# deneme4.net
KiCad netlist of a schematic drawn in EAGLE
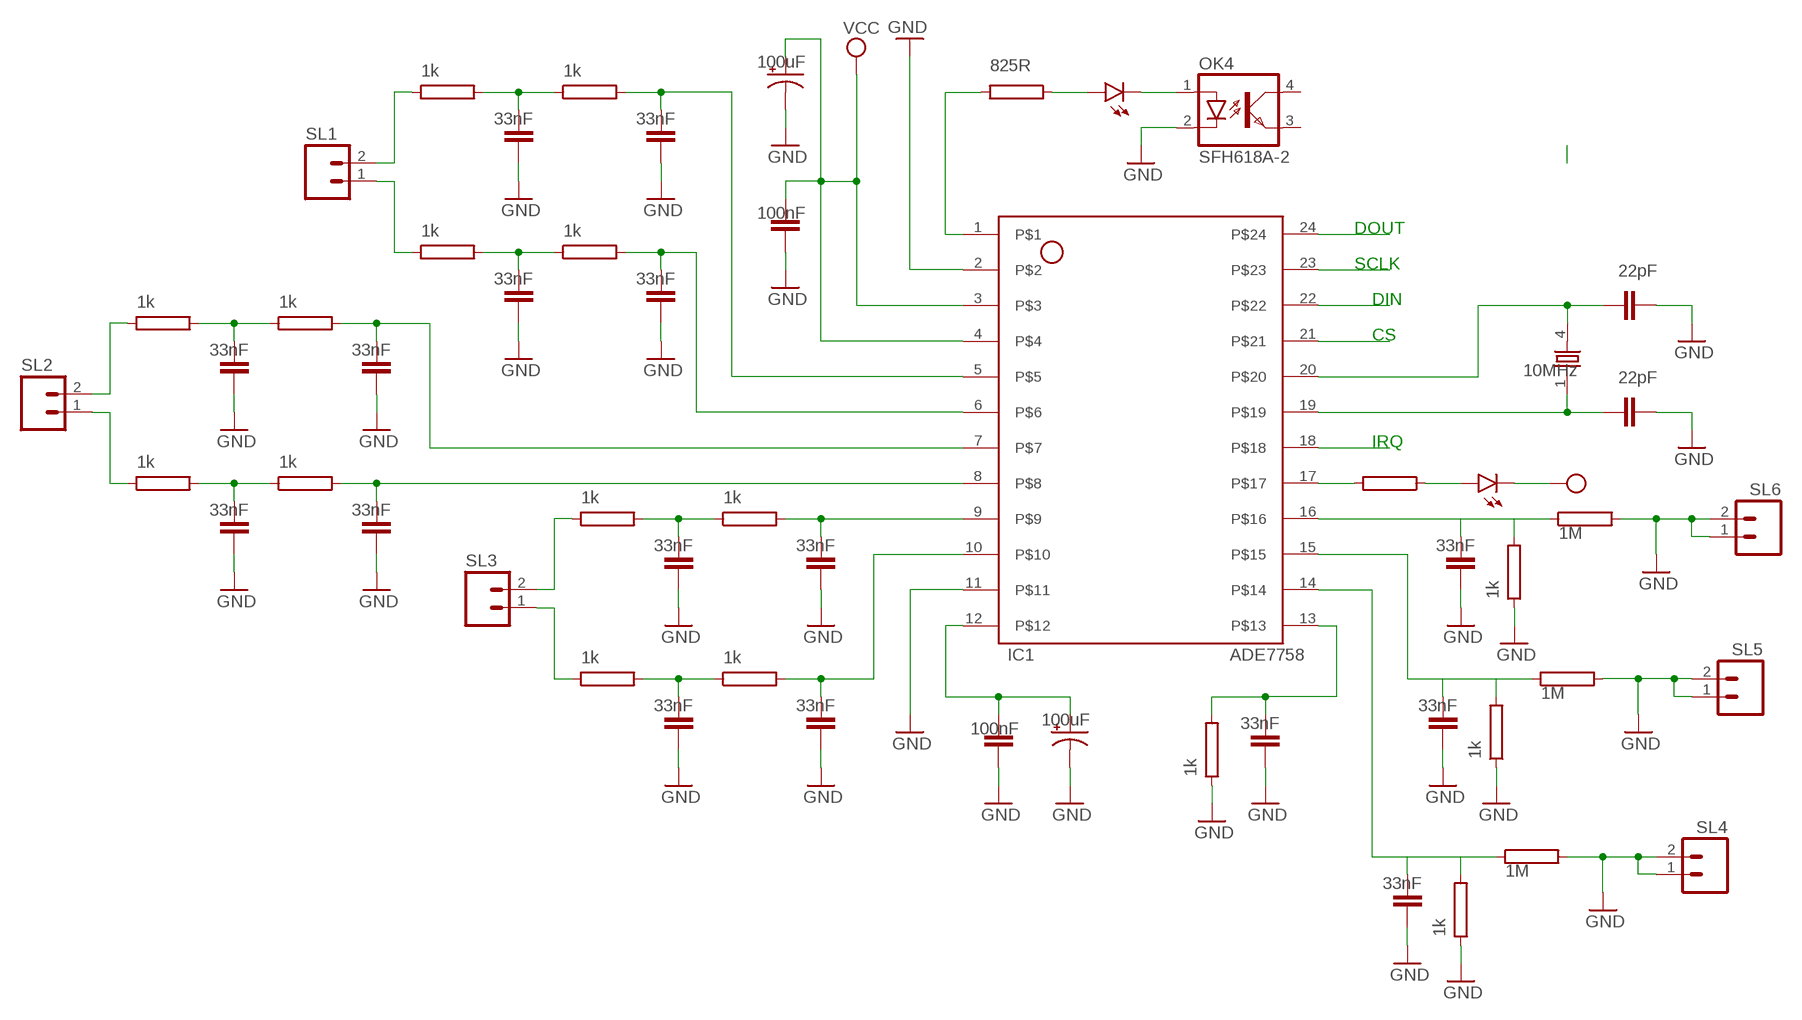
[diagram p0: schematic, sheet 1]

(export (version "E")
  (design (tool "Eeschema 10.0.6"))
  (components
    (comp (ref "C1")
      (value "100nF")
      (footprint "eagle-import:C2.5-3")
      (libsource (lib "eagle-import") (part "C2,5-3"))
    )
    (comp (ref "C2")
      (value "33nF")
      (footprint "eagle-import:C2.5-3")
      (libsource (lib "eagle-import") (part "C2,5-3"))
    )
    (comp (ref "C4")
      (value "33nF")
      (footprint "eagle-import:C2.5-3")
      (libsource (lib "eagle-import") (part "C2,5-3"))
    )
    (comp (ref "C5")
      (value "33nF")
      (footprint "eagle-import:C2.5-3")
      (libsource (lib "eagle-import") (part "C2,5-3"))
    )
    (comp (ref "C6")
      (value "33nF")
      (footprint "eagle-import:C2.5-3")
      (libsource (lib "eagle-import") (part "C2,5-3"))
    )
    (comp (ref "C7")
      (value "33nF")
      (footprint "eagle-import:C2.5-3")
      (libsource (lib "eagle-import") (part "C2,5-3"))
    )
    (comp (ref "C8")
      (value "22pF")
      (footprint "eagle-import:C2.5-3")
      (libsource (lib "eagle-import") (part "C2,5-3"))
    )
    (comp (ref "C9")
      (value "22pF")
      (footprint "eagle-import:C2.5-3")
      (libsource (lib "eagle-import") (part "C2,5-3"))
    )
    (comp (ref "C14")
      (value "100uF")
      (footprint "eagle-import:085CS_1AR")
      (libsource (lib "eagle-import") (part "CPOL-US085CS-1AR"))
    )
    (comp (ref "C16")
      (value "33nF")
      (footprint "eagle-import:C2.5-3")
      (libsource (lib "eagle-import") (part "C2,5-3"))
    )
    (comp (ref "C17")
      (value "33nF")
      (footprint "eagle-import:C2.5-3")
      (libsource (lib "eagle-import") (part "C2,5-3"))
    )
    (comp (ref "C18")
      (value "33nF")
      (footprint "eagle-import:C2.5-3")
      (libsource (lib "eagle-import") (part "C2,5-3"))
    )
    (comp (ref "C19")
      (value "33nF")
      (footprint "eagle-import:C2.5-3")
      (libsource (lib "eagle-import") (part "C2,5-3"))
    )
    (comp (ref "C20")
      (value "33nF")
      (footprint "eagle-import:C2.5-3")
      (libsource (lib "eagle-import") (part "C2,5-3"))
    )
    (comp (ref "C21")
      (value "33nF")
      (footprint "eagle-import:C2.5-3")
      (libsource (lib "eagle-import") (part "C2,5-3"))
    )
    (comp (ref "C22")
      (value "33nF")
      (footprint "eagle-import:C2.5-3")
      (libsource (lib "eagle-import") (part "C2,5-3"))
    )
    (comp (ref "C23")
      (value "100uF")
      (footprint "eagle-import:085CS_1AR")
      (libsource (lib "eagle-import") (part "CPOL-US085CS-1AR"))
    )
    (comp (ref "C24")
      (value "100nF")
      (footprint "eagle-import:C2.5-3")
      (libsource (lib "eagle-import") (part "C2,5-3"))
    )
    (comp (ref "C25")
      (value "33nF")
      (footprint "eagle-import:C2.5-3")
      (libsource (lib "eagle-import") (part "C2,5-3"))
    )
    (comp (ref "C26")
      (value "33nF")
      (footprint "eagle-import:C2.5-3")
      (libsource (lib "eagle-import") (part "C2,5-3"))
    )
    (comp (ref "C27")
      (value "33nF")
      (footprint "eagle-import:C2.5-3")
      (libsource (lib "eagle-import") (part "C2,5-3"))
    )
    (comp (ref "C28")
      (value "33nF")
      (footprint "eagle-import:C2.5-3")
      (libsource (lib "eagle-import") (part "C2,5-3"))
    )
    (comp (ref "IC1")
      (value "ADE7758")
      (footprint "eagle-import:ADE7758ARWZ")
      (fields (field (name "MF") "ADI Electronics"))
      (libsource (lib "eagle-import") (part "ADE7758"))
    )
    (comp (ref "LED1")
      (value "LAP4-BOTTOM")
      (footprint "eagle-import:P47F-BOTTOM")
      (libsource (lib "eagle-import") (part "P4-BOTTOMLA"))
    )
    (comp (ref "LED2")
      (value "LAP4-BOTTOM")
      (footprint "eagle-import:P47F-BOTTOM")
      (libsource (lib "eagle-import") (part "P4-BOTTOMLA"))
    )
    (comp (ref "OK4")
      (value "SFH618A-2")
      (footprint "eagle-import:DIP4")
      (fields (field (name "MF") "VISHAY/TELEFUNKEN"))
      (libsource (lib "eagle-import") (part "SFH618?A-2"))
    )
    (comp (ref "Q1")
      (value "10MHz")
      (footprint "eagle-import:86SMX")
      (fields (field (name "MF") "C-MAC  FREQUENCY PRODUCTS LTD") (field (name "MPN") "XTAL003321- 86SMX"))
      (libsource (lib "eagle-import") (part "86SMX"))
    )
    (comp (ref "R1")
      (value "825R")
      (footprint "eagle-import:TO-247-2V")
      (libsource (lib "eagle-import") (part "RMG100-V"))
    )
    (comp (ref "R2")
      (value "1k")
      (footprint "eagle-import:TO-247-2V")
      (libsource (lib "eagle-import") (part "RMG100-V"))
    )
    (comp (ref "R3")
      (value "1k")
      (footprint "eagle-import:TO-247-2V")
      (libsource (lib "eagle-import") (part "RMG100-V"))
    )
    (comp (ref "R4")
      (value "1k")
      (footprint "eagle-import:TO-247-2V")
      (libsource (lib "eagle-import") (part "RMG100-V"))
    )
    (comp (ref "R5")
      (value "1k")
      (footprint "eagle-import:TO-247-2V")
      (libsource (lib "eagle-import") (part "RMG100-V"))
    )
    (comp (ref "R6")
      (value "1k")
      (footprint "eagle-import:TO-247-2V")
      (libsource (lib "eagle-import") (part "RMG100-V"))
    )
    (comp (ref "R7")
      (value "1k")
      (footprint "eagle-import:TO-247-2V")
      (libsource (lib "eagle-import") (part "RMG100-V"))
    )
    (comp (ref "R8")
      (value "1k")
      (footprint "eagle-import:TO-247-2V")
      (libsource (lib "eagle-import") (part "RMG100-V"))
    )
    (comp (ref "R9")
      (value "1k")
      (footprint "eagle-import:TO-247-2V")
      (libsource (lib "eagle-import") (part "RMG100-V"))
    )
    (comp (ref "R10")
      (value "1k")
      (footprint "eagle-import:TO-247-2V")
      (libsource (lib "eagle-import") (part "RMG100-V"))
    )
    (comp (ref "R11")
      (value "1k")
      (footprint "eagle-import:TO-247-2V")
      (libsource (lib "eagle-import") (part "RMG100-V"))
    )
    (comp (ref "R12")
      (value "1k")
      (footprint "eagle-import:TO-247-2V")
      (libsource (lib "eagle-import") (part "RMG100-V"))
    )
    (comp (ref "R13")
      (value "1k")
      (footprint "eagle-import:TO-247-2V")
      (libsource (lib "eagle-import") (part "RMG100-V"))
    )
    (comp (ref "R14")
      (value "1k")
      (footprint "eagle-import:TO-247-2V")
      (libsource (lib "eagle-import") (part "RMG100-V"))
    )
    (comp (ref "R15")
      (value "1k")
      (footprint "eagle-import:TO-247-2V")
      (libsource (lib "eagle-import") (part "RMG100-V"))
    )
    (comp (ref "R16")
      (value "1M")
      (footprint "eagle-import:TO-247-2V")
      (libsource (lib "eagle-import") (part "RMG100-V"))
    )
    (comp (ref "R17")
      (value "1k")
      (footprint "eagle-import:TO-247-2V")
      (libsource (lib "eagle-import") (part "RMG100-V"))
    )
    (comp (ref "R18")
      (value "1M")
      (footprint "eagle-import:TO-247-2V")
      (libsource (lib "eagle-import") (part "RMG100-V"))
    )
    (comp (ref "R19")
      (value "1k")
      (footprint "eagle-import:TO-247-2V")
      (libsource (lib "eagle-import") (part "RMG100-V"))
    )
    (comp (ref "R20")
      (value "1M")
      (footprint "eagle-import:TO-247-2V")
      (libsource (lib "eagle-import") (part "RMG100-V"))
    )
    (comp (ref "R21")
      (value "825R")
      (footprint "eagle-import:TO-247-2V")
      (libsource (lib "eagle-import") (part "RMG100-V"))
    )
    (comp (ref "SL1")
      (value "M02")
      (footprint "eagle-import:02P")
      (libsource (lib "eagle-import") (part "M02"))
    )
    (comp (ref "SL2")
      (value "M02")
      (footprint "eagle-import:02P")
      (libsource (lib "eagle-import") (part "M02"))
    )
    (comp (ref "SL3")
      (value "M02")
      (footprint "eagle-import:02P")
      (libsource (lib "eagle-import") (part "M02"))
    )
    (comp (ref "SL4")
      (value "M02")
      (footprint "eagle-import:02P")
      (libsource (lib "eagle-import") (part "M02"))
    )
    (comp (ref "SL5")
      (value "M02")
      (footprint "eagle-import:02P")
      (libsource (lib "eagle-import") (part "M02"))
    )
    (comp (ref "SL6")
      (value "M02")
      (footprint "eagle-import:02P")
      (libsource (lib "eagle-import") (part "M02"))
    )
  )
  (nets
    (net (code "1") (name "GND") (class "Default")
      (node (ref "C1") (pin "1") (pinfunction "1_1") (pintype "passive"))
      (node (ref "C14") (pin "-") (pinfunction "-_-") (pintype "passive"))
      (node (ref "C16") (pin "2") (pinfunction "2_2") (pintype "passive"))
      (node (ref "C17") (pin "2") (pinfunction "2_2") (pintype "passive"))
      (node (ref "C18") (pin "2") (pinfunction "2_2") (pintype "passive"))
      (node (ref "C19") (pin "2") (pinfunction "2_2") (pintype "passive"))
      (node (ref "C2") (pin "2") (pinfunction "2_2") (pintype "passive"))
      (node (ref "C20") (pin "2") (pinfunction "2_2") (pintype "passive"))
      (node (ref "C21") (pin "2") (pinfunction "2_2") (pintype "passive"))
      (node (ref "C22") (pin "2") (pinfunction "2_2") (pintype "passive"))
      (node (ref "C23") (pin "-") (pinfunction "-_-") (pintype "passive"))
      (node (ref "C24") (pin "1") (pinfunction "1_1") (pintype "passive"))
      (node (ref "C25") (pin "2") (pinfunction "2_2") (pintype "passive"))
      (node (ref "C26") (pin "2") (pinfunction "2_2") (pintype "passive"))
      (node (ref "C27") (pin "2") (pinfunction "2_2") (pintype "passive"))
      (node (ref "C28") (pin "2") (pinfunction "2_2") (pintype "passive"))
      (node (ref "C4") (pin "2") (pinfunction "2_2") (pintype "passive"))
      (node (ref "C5") (pin "2") (pinfunction "2_2") (pintype "passive"))
      (node (ref "C6") (pin "2") (pinfunction "2_2") (pintype "passive"))
      (node (ref "C7") (pin "2") (pinfunction "2_2") (pintype "passive"))
      (node (ref "C8") (pin "2") (pinfunction "2_2") (pintype "passive"))
      (node (ref "C9") (pin "2") (pinfunction "2_2") (pintype "passive"))
      (node (ref "IC1") (pin "11") (pinfunction "P$11_11") (pintype "bidirectional"))
      (node (ref "IC1") (pin "2") (pinfunction "P$2_2") (pintype "bidirectional"))
      (node (ref "OK4") (pin "2") (pinfunction "C_2") (pintype "passive"))
      (node (ref "R14") (pin "1") (pinfunction "1_1") (pintype "passive"))
      (node (ref "R15") (pin "1") (pinfunction "1_1") (pintype "passive"))
      (node (ref "R16") (pin "2") (pinfunction "2_2") (pintype "passive"))
      (node (ref "R17") (pin "1") (pinfunction "1_1") (pintype "passive"))
      (node (ref "R18") (pin "2") (pinfunction "2_2") (pintype "passive"))
      (node (ref "R19") (pin "1") (pinfunction "1_1") (pintype "passive"))
      (node (ref "R20") (pin "2") (pinfunction "2_2") (pintype "passive"))
      (node (ref "SL4") (pin "1") (pinfunction "1_1") (pintype "passive"))
      (node (ref "SL4") (pin "2") (pinfunction "2_2") (pintype "passive"))
      (node (ref "SL5") (pin "1") (pinfunction "1_1") (pintype "passive"))
      (node (ref "SL5") (pin "2") (pinfunction "2_2") (pintype "passive"))
      (node (ref "SL6") (pin "1") (pinfunction "1_1") (pintype "passive"))
      (node (ref "SL6") (pin "2") (pinfunction "2_2") (pintype "passive"))
    )
    (net (code "2") (name "Net-(C16-Pad1)") (class "Default")
      (node (ref "C16") (pin "1") (pinfunction "1_1") (pintype "passive"))
      (node (ref "R2") (pin "1") (pinfunction "1_1") (pintype "passive"))
      (node (ref "R3") (pin "2") (pinfunction "2_2") (pintype "passive"))
    )
    (net (code "3") (name "Net-(C18-Pad1)") (class "Default")
      (node (ref "C18") (pin "1") (pinfunction "1_1") (pintype "passive"))
      (node (ref "R4") (pin "1") (pinfunction "1_1") (pintype "passive"))
      (node (ref "R5") (pin "2") (pinfunction "2_2") (pintype "passive"))
    )
    (net (code "4") (name "Net-(C20-Pad1)") (class "Default")
      (node (ref "C20") (pin "1") (pinfunction "1_1") (pintype "passive"))
      (node (ref "R6") (pin "1") (pinfunction "1_1") (pintype "passive"))
      (node (ref "R7") (pin "2") (pinfunction "2_2") (pintype "passive"))
    )
    (net (code "5") (name "Net-(C22-Pad1)") (class "Default")
      (node (ref "C22") (pin "1") (pinfunction "1_1") (pintype "passive"))
      (node (ref "R8") (pin "1") (pinfunction "1_1") (pintype "passive"))
      (node (ref "R9") (pin "2") (pinfunction "2_2") (pintype "passive"))
    )
    (net (code "6") (name "Net-(C26-Pad1)") (class "Default")
      (node (ref "C26") (pin "1") (pinfunction "1_1") (pintype "passive"))
      (node (ref "R10") (pin "1") (pinfunction "1_1") (pintype "passive"))
      (node (ref "R11") (pin "2") (pinfunction "2_2") (pintype "passive"))
    )
    (net (code "7") (name "Net-(C28-Pad1)") (class "Default")
      (node (ref "C28") (pin "1") (pinfunction "1_1") (pintype "passive"))
      (node (ref "R12") (pin "1") (pinfunction "1_1") (pintype "passive"))
      (node (ref "R13") (pin "2") (pinfunction "2_2") (pintype "passive"))
    )
    (net (code "8") (name "Net-(IC1-P$1)") (class "Default")
      (node (ref "IC1") (pin "1") (pinfunction "P$1_1") (pintype "bidirectional"))
      (node (ref "R1") (pin "2") (pinfunction "2_2") (pintype "passive"))
    )
    (net (code "9") (name "Net-(IC1-P$5)") (class "Default")
      (node (ref "C2") (pin "1") (pinfunction "1_1") (pintype "passive"))
      (node (ref "IC1") (pin "5") (pinfunction "P$5_5") (pintype "bidirectional"))
      (node (ref "R2") (pin "2") (pinfunction "2_2") (pintype "passive"))
    )
    (net (code "10") (name "Net-(IC1-P$6)") (class "Default")
      (node (ref "C17") (pin "1") (pinfunction "1_1") (pintype "passive"))
      (node (ref "IC1") (pin "6") (pinfunction "P$6_6") (pintype "bidirectional"))
      (node (ref "R4") (pin "2") (pinfunction "2_2") (pintype "passive"))
    )
    (net (code "11") (name "Net-(IC1-P$7)") (class "Default")
      (node (ref "C19") (pin "1") (pinfunction "1_1") (pintype "passive"))
      (node (ref "IC1") (pin "7") (pinfunction "P$7_7") (pintype "bidirectional"))
      (node (ref "R6") (pin "2") (pinfunction "2_2") (pintype "passive"))
    )
    (net (code "12") (name "Net-(IC1-P$8)") (class "Default")
      (node (ref "C21") (pin "1") (pinfunction "1_1") (pintype "passive"))
      (node (ref "IC1") (pin "8") (pinfunction "P$8_8") (pintype "bidirectional"))
      (node (ref "R8") (pin "2") (pinfunction "2_2") (pintype "passive"))
    )
    (net (code "13") (name "Net-(IC1-P$9)") (class "Default")
      (node (ref "C25") (pin "1") (pinfunction "1_1") (pintype "passive"))
      (node (ref "IC1") (pin "9") (pinfunction "P$9_9") (pintype "bidirectional"))
      (node (ref "R10") (pin "2") (pinfunction "2_2") (pintype "passive"))
    )
    (net (code "14") (name "Net-(IC1-P$10)") (class "Default")
      (node (ref "C27") (pin "1") (pinfunction "1_1") (pintype "passive"))
      (node (ref "IC1") (pin "10") (pinfunction "P$10_10") (pintype "bidirectional"))
      (node (ref "R12") (pin "2") (pinfunction "2_2") (pintype "passive"))
    )
    (net (code "15") (name "Net-(IC1-P$12)") (class "Default")
      (node (ref "C23") (pin "+") (pinfunction "+_+") (pintype "passive"))
      (node (ref "C24") (pin "2") (pinfunction "2_2") (pintype "passive"))
      (node (ref "IC1") (pin "12") (pinfunction "P$12_12") (pintype "bidirectional"))
    )
    (net (code "16") (name "Net-(IC1-P$13)") (class "Default")
      (node (ref "C4") (pin "1") (pinfunction "1_1") (pintype "passive"))
      (node (ref "IC1") (pin "13") (pinfunction "P$13_13") (pintype "bidirectional"))
      (node (ref "R14") (pin "2") (pinfunction "2_2") (pintype "passive"))
    )
    (net (code "17") (name "Net-(IC1-P$14)") (class "Default")
      (node (ref "IC1") (pin "14") (pinfunction "P$14_14") (pintype "bidirectional"))
      (node (ref "R18") (pin "1") (pinfunction "1_1") (pintype "passive"))
    )
    (net (code "18") (name "Net-(IC1-P$15)") (class "Default")
      (node (ref "IC1") (pin "15") (pinfunction "P$15_15") (pintype "bidirectional"))
      (node (ref "R16") (pin "1") (pinfunction "1_1") (pintype "passive"))
    )
    (net (code "19") (name "Net-(IC1-P$16)") (class "Default")
      (node (ref "IC1") (pin "16") (pinfunction "P$16_16") (pintype "bidirectional"))
      (node (ref "R20") (pin "1") (pinfunction "1_1") (pintype "passive"))
    )
    (net (code "20") (name "Net-(IC1-P$17)") (class "Default")
      (node (ref "IC1") (pin "17") (pinfunction "P$17_17") (pintype "bidirectional"))
      (node (ref "R21") (pin "2") (pinfunction "2_2") (pintype "passive"))
    )
    (net (code "21") (name "Net-(IC1-P$19)") (class "Default")
      (node (ref "C8") (pin "1") (pinfunction "1_1") (pintype "passive"))
      (node (ref "IC1") (pin "19") (pinfunction "P$19_19") (pintype "bidirectional"))
      (node (ref "Q1") (pin "1") (pinfunction "1_1") (pintype "passive"))
    )
    (net (code "22") (name "Net-(IC1-P$20)") (class "Default")
      (node (ref "C9") (pin "1") (pinfunction "1_1") (pintype "passive"))
      (node (ref "IC1") (pin "20") (pinfunction "P$20_20") (pintype "bidirectional"))
      (node (ref "Q1") (pin "4") (pinfunction "2_4") (pintype "passive"))
    )
    (net (code "23") (name "Net-(LED1-PadA)") (class "Default")
      (node (ref "LED1") (pin "A") (pinfunction "A_A") (pintype "passive"))
      (node (ref "R1") (pin "1") (pinfunction "1_1") (pintype "passive"))
    )
    (net (code "24") (name "Net-(LED2-PadA)") (class "Default")
      (node (ref "LED2") (pin "A") (pinfunction "A_A") (pintype "passive"))
      (node (ref "R21") (pin "1") (pinfunction "1_1") (pintype "passive"))
    )
    (net (code "25") (name "Net-(OK4-A)") (class "Default")
      (node (ref "LED1") (pin "C") (pinfunction "C_C") (pintype "passive"))
      (node (ref "OK4") (pin "1") (pinfunction "A_1") (pintype "passive"))
    )
    (net (code "26") (name "Net-(R3-Pad1)") (class "Default")
      (node (ref "R3") (pin "1") (pinfunction "1_1") (pintype "passive"))
      (node (ref "SL1") (pin "2") (pinfunction "2_2") (pintype "passive"))
    )
    (net (code "27") (name "Net-(R5-Pad1)") (class "Default")
      (node (ref "R5") (pin "1") (pinfunction "1_1") (pintype "passive"))
      (node (ref "SL1") (pin "1") (pinfunction "1_1") (pintype "passive"))
    )
    (net (code "28") (name "Net-(R7-Pad1)") (class "Default")
      (node (ref "R7") (pin "1") (pinfunction "1_1") (pintype "passive"))
      (node (ref "SL2") (pin "2") (pinfunction "2_2") (pintype "passive"))
    )
    (net (code "29") (name "Net-(R9-Pad1)") (class "Default")
      (node (ref "R9") (pin "1") (pinfunction "1_1") (pintype "passive"))
      (node (ref "SL2") (pin "1") (pinfunction "1_1") (pintype "passive"))
    )
    (net (code "30") (name "Net-(R11-Pad1)") (class "Default")
      (node (ref "R11") (pin "1") (pinfunction "1_1") (pintype "passive"))
      (node (ref "SL3") (pin "2") (pinfunction "2_2") (pintype "passive"))
    )
    (net (code "31") (name "Net-(R13-Pad1)") (class "Default")
      (node (ref "R13") (pin "1") (pinfunction "1_1") (pintype "passive"))
      (node (ref "SL3") (pin "1") (pinfunction "1_1") (pintype "passive"))
    )
    (net (code "32") (name "VCC") (class "Default")
      (node (ref "C1") (pin "2") (pinfunction "2_2") (pintype "passive"))
      (node (ref "C14") (pin "+") (pinfunction "+_+") (pintype "passive"))
      (node (ref "IC1") (pin "3") (pinfunction "P$3_3") (pintype "bidirectional"))
      (node (ref "IC1") (pin "4") (pinfunction "P$4_4") (pintype "bidirectional"))
      (node (ref "LED2") (pin "C") (pinfunction "C_C") (pintype "passive"))
    )
    (net (code "33") (name "unconnected-(C5-Pad1)") (class "Default")
      (node (ref "C5") (pin "1") (pinfunction "1_1") (pintype "passive"))
    )
    (net (code "34") (name "unconnected-(C6-Pad1)") (class "Default")
      (node (ref "C6") (pin "1") (pinfunction "1_1") (pintype "passive"))
    )
    (net (code "35") (name "unconnected-(C7-Pad1)") (class "Default")
      (node (ref "C7") (pin "1") (pinfunction "1_1") (pintype "passive"))
    )
    (net (code "36") (name "unconnected-(IC1-P$18-Pad18)") (class "Default")
      (node (ref "IC1") (pin "18") (pinfunction "P$18_18") (pintype "bidirectional"))
    )
    (net (code "37") (name "unconnected-(IC1-P$21-Pad21)") (class "Default")
      (node (ref "IC1") (pin "21") (pinfunction "P$21_21") (pintype "bidirectional"))
    )
    (net (code "38") (name "unconnected-(IC1-P$22-Pad22)") (class "Default")
      (node (ref "IC1") (pin "22") (pinfunction "P$22_22") (pintype "bidirectional"))
    )
    (net (code "39") (name "unconnected-(IC1-P$23-Pad23)") (class "Default")
      (node (ref "IC1") (pin "23") (pinfunction "P$23_23") (pintype "bidirectional"))
    )
    (net (code "40") (name "unconnected-(IC1-P$24-Pad24)") (class "Default")
      (node (ref "IC1") (pin "24") (pinfunction "P$24_24") (pintype "bidirectional"))
    )
    (net (code "41") (name "unconnected-(OK4-COL-Pad4)") (class "Default")
      (node (ref "OK4") (pin "4") (pinfunction "COL_4") (pintype "passive"))
    )
    (net (code "42") (name "unconnected-(OK4-EMIT-Pad3)") (class "Default")
      (node (ref "OK4") (pin "3") (pinfunction "EMIT_3") (pintype "passive"))
    )
    (net (code "43") (name "unconnected-(R15-Pad2)") (class "Default")
      (node (ref "R15") (pin "2") (pinfunction "2_2") (pintype "passive"))
    )
    (net (code "44") (name "unconnected-(R17-Pad2)") (class "Default")
      (node (ref "R17") (pin "2") (pinfunction "2_2") (pintype "passive"))
    )
    (net (code "45") (name "unconnected-(R19-Pad2)") (class "Default")
      (node (ref "R19") (pin "2") (pinfunction "2_2") (pintype "passive"))
    )
  )
)
